# Sheet1.net
KiCad netlist of a schematic drawn in Altium Designer
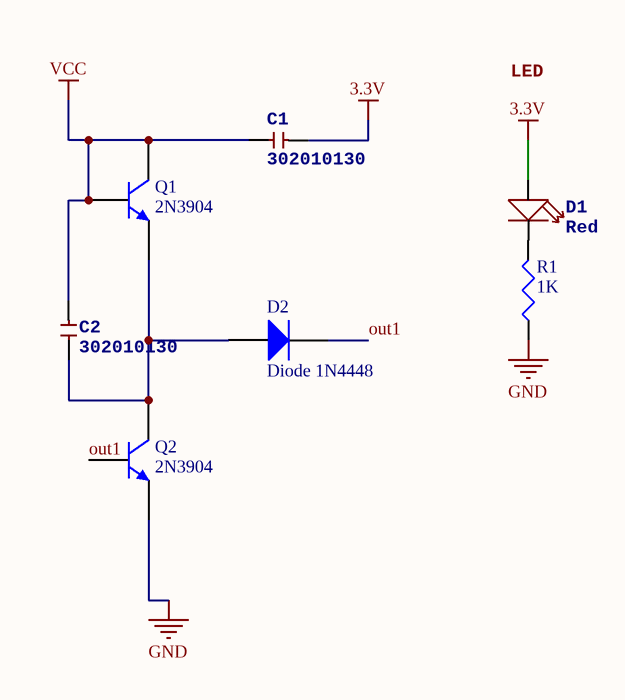
[diagram p0: Sheet1.SchDoc]

(export (version "E")
  (design (tool "Eeschema 10.0.6"))
  (components
    (comp (ref "C1")
      (value "302010130")
      (footprint "C0603")
      (fields (field (name "MPN") "GRM1885C2A471JA01D"))
      (libsource (lib "Seeed-OPL-Capacitor") (part "CERAMIC-470PF-100V-5%-NP0(0603)"))
    )
    (comp (ref "C2")
      (value "302010130")
      (footprint "C0603")
      (fields (field (name "MPN") "GRM1885C2A471JA01D"))
      (libsource (lib "Seeed-OPL-Capacitor") (part "CERAMIC-470PF-100V-5%-NP0(0603)"))
    )
    (comp (ref "D1") (value "Red") (footprint "LED-0603") (libsource (lib "Discrete") (part "LED-0603")))
    (comp (ref "D2")
      (value "Diode 1N4448")
      (footprint "DO-35")
      (description "High Conductance Fast Diode")
      (fields (field (name "PUBLISHER") "Altium Limited"))
      (libsource (lib "Miscellaneous Devices") (part "Diode 1N4448"))
    )
    (comp (ref "Q1")
      (value "2N3904")
      (footprint "TO-92A")
      (description "NPN General Purpose Amplifier")
      (fields (field (name "PUBLISHER") "Altium Limited"))
      (libsource (lib "Miscellaneous Devices") (part "2N3904"))
    )
    (comp (ref "Q2")
      (value "2N3904")
      (footprint "TO-92A")
      (description "NPN General Purpose Amplifier")
      (fields (field (name "PUBLISHER") "Altium Limited"))
      (libsource (lib "Miscellaneous Devices") (part "2N3904"))
    )
    (comp (ref "R1")
      (value "1K")
      (footprint "J1-0603")
      (description "Resistor")
      (fields (field (name "Comment") "Res3") (field (name "PUBLISHER") "Altium Limited"))
      (libsource (lib "Miscellaneous Devices") (part "Res3"))
    )
  )
  (nets
    (net (code "1") (name "/out1") (class "Default")
      (node (ref "D2") (pin "2") (pinfunction "K_2") (pintype "passive"))
      (node (ref "Q2") (pin "2") (pinfunction "B_2") (pintype "passive"))
    )
    (net (code "2") (name "3.3V") (class "Default")
      (node (ref "C1") (pin "2") (pinfunction "2_2") (pintype "passive"))
      (node (ref "D1") (pin "+") (pinfunction "+_+") (pintype "passive"))
    )
    (net (code "3") (name "GND") (class "Default")
      (node (ref "Q2") (pin "1") (pinfunction "E_1") (pintype "passive"))
      (node (ref "R1") (pin "1") (pinfunction "1_1") (pintype "passive"))
    )
    (net (code "4") (name "Net-(D1-Pad-)") (class "Default")
      (node (ref "D1") (pin "-") (pinfunction "-_-") (pintype "passive"))
      (node (ref "R1") (pin "2") (pinfunction "2_2") (pintype "passive"))
    )
    (net (code "5") (name "Net-(D2-A)") (class "Default")
      (node (ref "C2") (pin "1") (pinfunction "1_1") (pintype "passive"))
      (node (ref "D2") (pin "1") (pinfunction "A_1") (pintype "passive"))
      (node (ref "Q1") (pin "1") (pinfunction "E_1") (pintype "passive"))
      (node (ref "Q2") (pin "3") (pinfunction "C_3") (pintype "passive"))
    )
    (net (code "6") (name "VCC") (class "Default")
      (node (ref "C1") (pin "1") (pinfunction "1_1") (pintype "passive"))
      (node (ref "C2") (pin "2") (pinfunction "2_2") (pintype "passive"))
      (node (ref "Q1") (pin "2") (pinfunction "B_2") (pintype "passive"))
      (node (ref "Q1") (pin "3") (pinfunction "C_3") (pintype "passive"))
    )
  )
)
